# Step_Down.net
KiCad netlist of a schematic drawn in Altium Designer
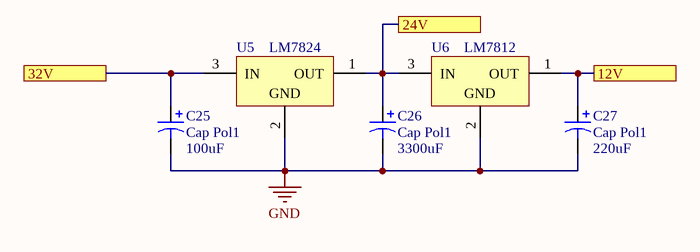
[diagram p0: Step Down.SchDoc]

(export (version "E")
  (design (tool "Eeschema 10.0.6"))
  (components
    (comp (ref "C25")
      (value "Cap Pol1")
      (footprint "RB7.6-15")
      (description "Polarized Capacitor (Radial)")
      (fields (field (name "ALTIUM_VALUE") "100uF") (field (name "PUBLISHER") "Altium Limited"))
      (libsource (lib "Miscellaneous Devices") (part "Cap Pol1"))
    )
    (comp (ref "C26")
      (value "Cap Pol1")
      (footprint "RB7.6-15")
      (description "Polarized Capacitor (Radial)")
      (fields (field (name "ALTIUM_VALUE") "3300uF") (field (name "PUBLISHER") "Altium Limited"))
      (libsource (lib "Miscellaneous Devices") (part "Cap Pol1"))
    )
    (comp (ref "C27")
      (value "Cap Pol1")
      (footprint "RB7.6-15")
      (description "Polarized Capacitor (Radial)")
      (fields (field (name "ALTIUM_VALUE") "220uF") (field (name "PUBLISHER") "Altium Limited"))
      (libsource (lib "Miscellaneous Devices") (part "Cap Pol1"))
    )
    (comp (ref "U5")
      (value "LM7824")
      (footprint "Z03A")
      (description "3-Terminal Positive Regulators, 3-pin TO-92")
      (fields
        (field (name "PARTNUMBER") "LM78L12ACZ")
        (field (name "MANUFACTURER") "National Semiconductor")
        (field (name "PUBLISHER") "Altium Limited")
      )
      (libsource (lib "NSC LDO") (part "LM78L12ACZ"))
    )
    (comp (ref "U6")
      (value "LM7812")
      (footprint "Z03A")
      (description "3-Terminal Positive Regulators, 3-pin TO-92")
      (fields
        (field (name "PARTNUMBER") "LM78L12ACZ")
        (field (name "MANUFACTURER") "National Semiconductor")
        (field (name "PUBLISHER") "Altium Limited")
      )
      (libsource (lib "NSC LDO") (part "LM78L12ACZ"))
    )
  )
  (nets
    (net (code "1") (name "/12V") (class "Default")
      (node (ref "C27") (pin "1") (pinfunction "1_1") (pintype "passive"))
      (node (ref "U6") (pin "1") (pinfunction "OUT_1") (pintype "power_in"))
    )
    (net (code "2") (name "/24V") (class "Default")
      (node (ref "C26") (pin "1") (pinfunction "1_1") (pintype "passive"))
      (node (ref "U5") (pin "1") (pinfunction "OUT_1") (pintype "power_in"))
      (node (ref "U6") (pin "3") (pinfunction "IN_3") (pintype "power_in"))
    )
    (net (code "3") (name "/32V") (class "Default")
      (node (ref "C25") (pin "1") (pinfunction "1_1") (pintype "passive"))
      (node (ref "U5") (pin "3") (pinfunction "IN_3") (pintype "power_in"))
    )
    (net (code "4") (name "GND") (class "Default")
      (node (ref "C25") (pin "2") (pinfunction "2_2") (pintype "passive"))
      (node (ref "C26") (pin "2") (pinfunction "2_2") (pintype "passive"))
      (node (ref "C27") (pin "2") (pinfunction "2_2") (pintype "passive"))
      (node (ref "U5") (pin "2") (pinfunction "GND_2") (pintype "power_in"))
      (node (ref "U6") (pin "2") (pinfunction "GND_2") (pintype "power_in"))
    )
  )
)
